# ADC1.net
KiCad netlist of a schematic drawn in Altium Designer
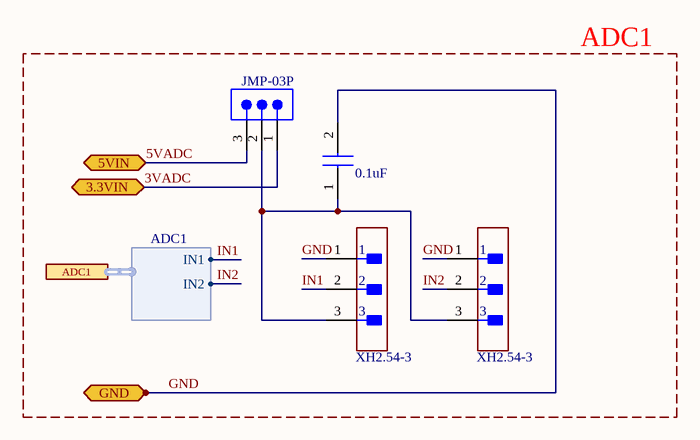
[diagram p0: ADC1.SchDoc]

(export (version "E")
  (design (tool "Eeschema 10.0.6"))
  (components
    (comp (ref "ADC1-1")
      (value "XH2.54-3")
      (footprint "XH2.54-3")
      (description "JST XH2.54-3pin")
      (libsource (lib "Components_Robots") (part "XH2.54-3"))
    )
    (comp (ref "ADC1-2")
      (value "XH2.54-3")
      (footprint "XH2.54-3")
      (description "JST XH2.54-3pin")
      (libsource (lib "Components_Robots") (part "XH2.54-3"))
    )
    (comp (ref "CAPADC")
      (value "0.1uF")
      (footprint "CAP0805")
      (description "CAP-SMD0805")
      (libsource (lib "Components_Robots") (part "CAP0805"))
    )
    (comp (ref "JMPADC1")
      (value "JMP-03P")
      (footprint "JMP-03P")
      (description "PLS-1x3")
      (libsource (lib "Components_Robots") (part "JMP-03P"))
    )
  )
  (nets
    (net (code "2") (name "/3VADC") (class "Default")
      (node (ref "JMPADC1") (pin "1") (pinfunction "1_1") (pintype "passive"))
    )
    (net (code "3") (name "/5VADC") (class "Default")
      (node (ref "JMPADC1") (pin "3") (pinfunction "3_3") (pintype "passive"))
    )
    (net (code "4") (name "/GND") (class "Default")
      (node (ref "ADC1-1") (pin "1") (pinfunction "1_1") (pintype "passive"))
      (node (ref "ADC1-2") (pin "1") (pinfunction "1_1") (pintype "passive"))
      (node (ref "CAPADC") (pin "2") (pinfunction "2_2") (pintype "passive"))
    )
    (net (code "5") (name "/IN1") (class "Default")
      (node (ref "ADC1-1") (pin "2") (pinfunction "2_2") (pintype "passive"))
    )
    (net (code "6") (name "/IN2") (class "Default")
      (node (ref "ADC1-2") (pin "2") (pinfunction "2_2") (pintype "passive"))
    )
    (net (code "8") (name "Net-(ADC1-1-Pad3)") (class "Default")
      (node (ref "ADC1-1") (pin "3") (pinfunction "3_3") (pintype "passive"))
      (node (ref "ADC1-2") (pin "3") (pinfunction "3_3") (pintype "passive"))
      (node (ref "CAPADC") (pin "1") (pinfunction "1_1") (pintype "passive"))
      (node (ref "JMPADC1") (pin "2") (pinfunction "2_2") (pintype "passive"))
    )
  )
)
